# Buttons.net
KiCad netlist of a schematic drawn in Altium Designer
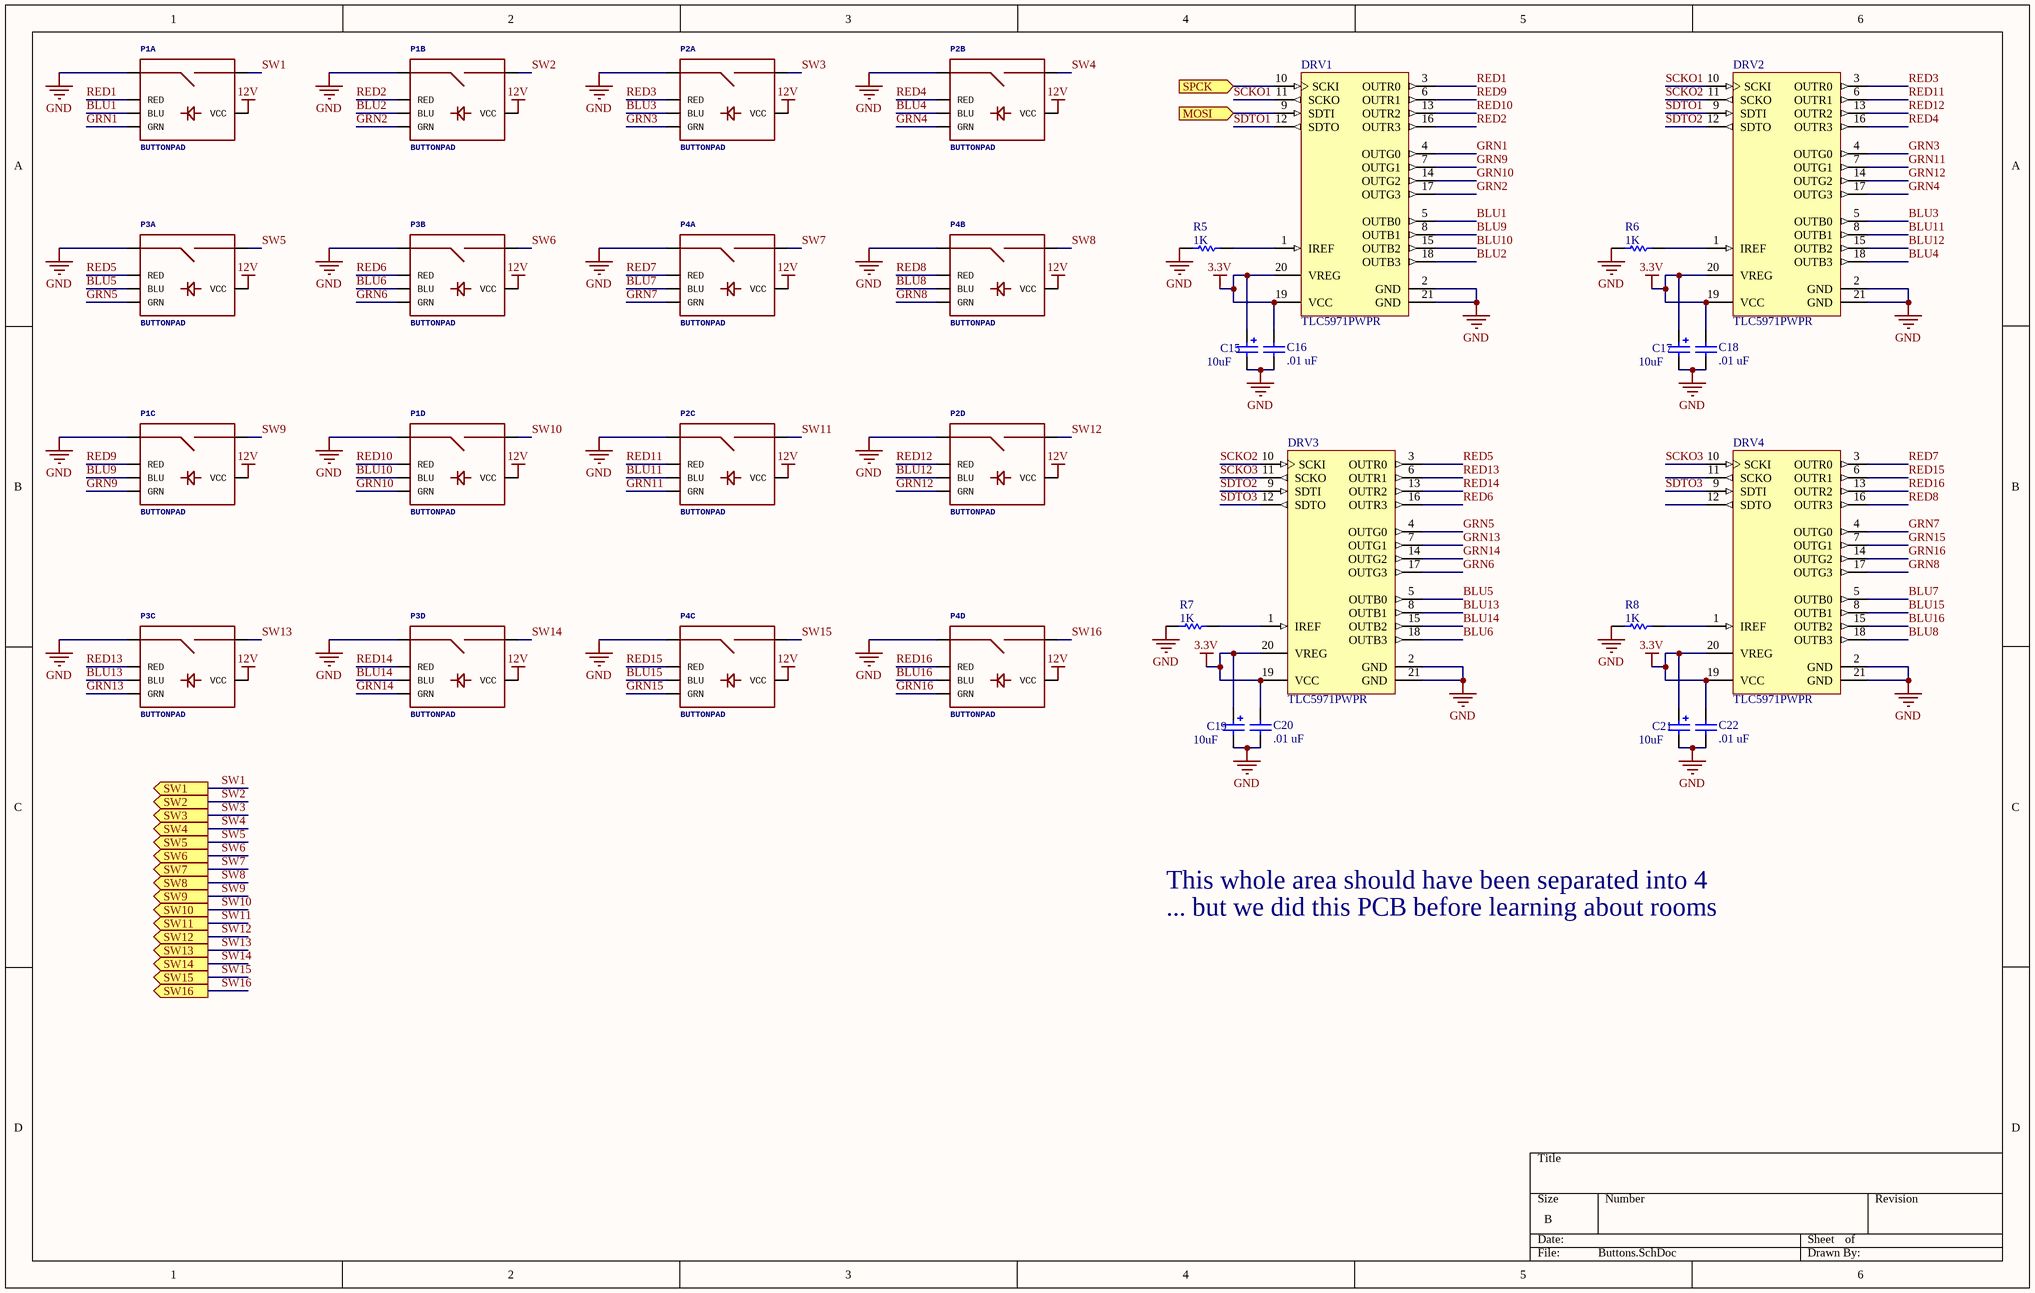
[diagram p0: Buttons.SchDoc]

(export (version "E")
  (design (tool "Eeschema 10.0.6"))
  (components
    (comp (ref "C15")
      (value "10uF")
      (footprint "RAD-0.2")
      (description "Polarized Capacitor (Axial)")
      (fields (field (name "PUBLISHER") "Altium Limited"))
      (libsource (lib "Miscellaneous Devices") (part "Cap Pol2"))
    )
    (comp (ref "C16")
      (value ".01 uF")
      (footprint "C0805")
      (description "Capacitor")
      (fields (field (name "Comment") "Cap") (field (name "PUBLISHER") "Altium Limited"))
      (libsource (lib "Miscellaneous Devices") (part "Cap"))
    )
    (comp (ref "C17")
      (value "10uF")
      (footprint "RAD-0.2")
      (description "Polarized Capacitor (Axial)")
      (fields (field (name "PUBLISHER") "Altium Limited"))
      (libsource (lib "Miscellaneous Devices") (part "Cap Pol2"))
    )
    (comp (ref "C18")
      (value ".01 uF")
      (footprint "C0805")
      (description "Capacitor")
      (fields (field (name "Comment") "Cap") (field (name "PUBLISHER") "Altium Limited"))
      (libsource (lib "Miscellaneous Devices") (part "Cap"))
    )
    (comp (ref "C19")
      (value "10uF")
      (footprint "RAD-0.2")
      (description "Polarized Capacitor (Axial)")
      (fields (field (name "PUBLISHER") "Altium Limited"))
      (libsource (lib "Miscellaneous Devices") (part "Cap Pol2"))
    )
    (comp (ref "C20")
      (value ".01 uF")
      (footprint "C0805")
      (description "Capacitor")
      (fields (field (name "Comment") "Cap") (field (name "PUBLISHER") "Altium Limited"))
      (libsource (lib "Miscellaneous Devices") (part "Cap"))
    )
    (comp (ref "C21")
      (value "10uF")
      (footprint "RAD-0.2")
      (description "Polarized Capacitor (Axial)")
      (fields (field (name "PUBLISHER") "Altium Limited"))
      (libsource (lib "Miscellaneous Devices") (part "Cap Pol2"))
    )
    (comp (ref "C22")
      (value ".01 uF")
      (footprint "C0805")
      (description "Capacitor")
      (fields (field (name "Comment") "Cap") (field (name "PUBLISHER") "Altium Limited"))
      (libsource (lib "Miscellaneous Devices") (part "Cap"))
    )
    (comp (ref "DRV1")
      (value "TLC5971PWPR")
      (footprint "TI-PWP20-2965X2290TP_N")
      (fields (field (name "MANUFACTURER") "Texas Instruments"))
      (libsource (lib "TI Power Management Lighting and Display") (part "TLC5971PWPR"))
    )
    (comp (ref "DRV2")
      (value "TLC5971PWPR")
      (footprint "TI-PWP20-2965X2290TP_N")
      (fields (field (name "MANUFACTURER") "Texas Instruments"))
      (libsource (lib "TI Power Management Lighting and Display") (part "TLC5971PWPR"))
    )
    (comp (ref "DRV3")
      (value "TLC5971PWPR")
      (footprint "TI-PWP20-2965X2290TP_N")
      (fields (field (name "MANUFACTURER") "Texas Instruments"))
      (libsource (lib "TI Power Management Lighting and Display") (part "TLC5971PWPR"))
    )
    (comp (ref "DRV4")
      (value "TLC5971PWPR")
      (footprint "TI-PWP20-2965X2290TP_N")
      (fields (field (name "MANUFACTURER") "Texas Instruments"))
      (libsource (lib "TI Power Management Lighting and Display") (part "TLC5971PWPR"))
    )
    (comp (ref "P1")
      (value "BUTTONPAD")
      (footprint "BUTTONPAD-2X2")
      (libsource (lib "Button_Pad_Breakout-v05") (part "BUTTONPAD-2X2"))
    )
    (comp (ref "P2")
      (value "BUTTONPAD")
      (footprint "BUTTONPAD-2X2")
      (libsource (lib "Button_Pad_Breakout-v05") (part "BUTTONPAD-2X2"))
    )
    (comp (ref "P3")
      (value "BUTTONPAD")
      (footprint "BUTTONPAD-2X2")
      (libsource (lib "Button_Pad_Breakout-v05") (part "BUTTONPAD-2X2"))
    )
    (comp (ref "P4")
      (value "BUTTONPAD")
      (footprint "BUTTONPAD-2X2")
      (libsource (lib "Button_Pad_Breakout-v05") (part "BUTTONPAD-2X2"))
    )
    (comp (ref "R5")
      (value "1K")
      (footprint "AXIAL-0.3")
      (description "Resistor")
      (fields (field (name "Comment") "R1") (field (name "PUBLISHER") "Altium Limited"))
      (libsource (lib "Miscellaneous Devices") (part "Res1"))
    )
    (comp (ref "R6")
      (value "1K")
      (footprint "AXIAL-0.3")
      (description "Resistor")
      (fields (field (name "Comment") "R2") (field (name "PUBLISHER") "Altium Limited"))
      (libsource (lib "Miscellaneous Devices") (part "Res1"))
    )
    (comp (ref "R7")
      (value "1K")
      (footprint "AXIAL-0.3")
      (description "Resistor")
      (fields (field (name "Comment") "R3") (field (name "PUBLISHER") "Altium Limited"))
      (libsource (lib "Miscellaneous Devices") (part "Res1"))
    )
    (comp (ref "R8")
      (value "1K")
      (footprint "AXIAL-0.3")
      (description "Resistor")
      (fields (field (name "Comment") "R4") (field (name "PUBLISHER") "Altium Limited"))
      (libsource (lib "Miscellaneous Devices") (part "Res1"))
    )
  )
  (nets
    (net (code "1") (name "/BLU1") (class "Default")
      (node (ref "DRV1") (pin "5") (pinfunction "OUTB0_5") (pintype "output"))
      (node (ref "P1") (pin "BLU1") (pinfunction "BLU_BLU1") (pintype "passive"))
    )
    (net (code "2") (name "/BLU2") (class "Default")
      (node (ref "DRV1") (pin "18") (pinfunction "OUTB3_18") (pintype "output"))
      (node (ref "P1") (pin "BLU2") (pinfunction "BLU_BLU2") (pintype "passive"))
    )
    (net (code "3") (name "/BLU3") (class "Default")
      (node (ref "DRV2") (pin "5") (pinfunction "OUTB0_5") (pintype "output"))
      (node (ref "P2") (pin "BLU1") (pinfunction "BLU_BLU1") (pintype "passive"))
    )
    (net (code "4") (name "/BLU4") (class "Default")
      (node (ref "DRV2") (pin "18") (pinfunction "OUTB3_18") (pintype "output"))
      (node (ref "P2") (pin "BLU2") (pinfunction "BLU_BLU2") (pintype "passive"))
    )
    (net (code "5") (name "/BLU5") (class "Default")
      (node (ref "DRV3") (pin "5") (pinfunction "OUTB0_5") (pintype "output"))
      (node (ref "P3") (pin "BLU1") (pinfunction "BLU_BLU1") (pintype "passive"))
    )
    (net (code "6") (name "/BLU6") (class "Default")
      (node (ref "DRV3") (pin "18") (pinfunction "OUTB3_18") (pintype "output"))
      (node (ref "P3") (pin "BLU2") (pinfunction "BLU_BLU2") (pintype "passive"))
    )
    (net (code "7") (name "/BLU7") (class "Default")
      (node (ref "DRV4") (pin "5") (pinfunction "OUTB0_5") (pintype "output"))
      (node (ref "P4") (pin "BLU1") (pinfunction "BLU_BLU1") (pintype "passive"))
    )
    (net (code "8") (name "/BLU8") (class "Default")
      (node (ref "DRV4") (pin "18") (pinfunction "OUTB3_18") (pintype "output"))
      (node (ref "P4") (pin "BLU2") (pinfunction "BLU_BLU2") (pintype "passive"))
    )
    (net (code "9") (name "/BLU9") (class "Default")
      (node (ref "DRV1") (pin "8") (pinfunction "OUTB1_8") (pintype "output"))
      (node (ref "P1") (pin "BLU3") (pinfunction "BLU_BLU3") (pintype "passive"))
    )
    (net (code "10") (name "/BLU10") (class "Default")
      (node (ref "DRV1") (pin "15") (pinfunction "OUTB2_15") (pintype "output"))
      (node (ref "P1") (pin "BLU4") (pinfunction "BLU_BLU4") (pintype "passive"))
    )
    (net (code "11") (name "/BLU11") (class "Default")
      (node (ref "DRV2") (pin "8") (pinfunction "OUTB1_8") (pintype "output"))
      (node (ref "P2") (pin "BLU3") (pinfunction "BLU_BLU3") (pintype "passive"))
    )
    (net (code "12") (name "/BLU12") (class "Default")
      (node (ref "DRV2") (pin "15") (pinfunction "OUTB2_15") (pintype "output"))
      (node (ref "P2") (pin "BLU4") (pinfunction "BLU_BLU4") (pintype "passive"))
    )
    (net (code "13") (name "/BLU13") (class "Default")
      (node (ref "DRV3") (pin "8") (pinfunction "OUTB1_8") (pintype "output"))
      (node (ref "P3") (pin "BLU3") (pinfunction "BLU_BLU3") (pintype "passive"))
    )
    (net (code "14") (name "/BLU14") (class "Default")
      (node (ref "DRV3") (pin "15") (pinfunction "OUTB2_15") (pintype "output"))
      (node (ref "P3") (pin "BLU4") (pinfunction "BLU_BLU4") (pintype "passive"))
    )
    (net (code "15") (name "/BLU15") (class "Default")
      (node (ref "DRV4") (pin "8") (pinfunction "OUTB1_8") (pintype "output"))
      (node (ref "P4") (pin "BLU3") (pinfunction "BLU_BLU3") (pintype "passive"))
    )
    (net (code "16") (name "/BLU16") (class "Default")
      (node (ref "DRV4") (pin "15") (pinfunction "OUTB2_15") (pintype "output"))
      (node (ref "P4") (pin "BLU4") (pinfunction "BLU_BLU4") (pintype "passive"))
    )
    (net (code "17") (name "/GRN1") (class "Default")
      (node (ref "DRV1") (pin "4") (pinfunction "OUTG0_4") (pintype "output"))
      (node (ref "P1") (pin "GRN1") (pinfunction "GRN_GRN1") (pintype "passive"))
    )
    (net (code "18") (name "/GRN2") (class "Default")
      (node (ref "DRV1") (pin "17") (pinfunction "OUTG3_17") (pintype "output"))
      (node (ref "P1") (pin "GRN2") (pinfunction "GRN_GRN2") (pintype "passive"))
    )
    (net (code "19") (name "/GRN3") (class "Default")
      (node (ref "DRV2") (pin "4") (pinfunction "OUTG0_4") (pintype "output"))
      (node (ref "P2") (pin "GRN1") (pinfunction "GRN_GRN1") (pintype "passive"))
    )
    (net (code "20") (name "/GRN4") (class "Default")
      (node (ref "DRV2") (pin "17") (pinfunction "OUTG3_17") (pintype "output"))
      (node (ref "P2") (pin "GRN2") (pinfunction "GRN_GRN2") (pintype "passive"))
    )
    (net (code "21") (name "/GRN5") (class "Default")
      (node (ref "DRV3") (pin "4") (pinfunction "OUTG0_4") (pintype "output"))
      (node (ref "P3") (pin "GRN1") (pinfunction "GRN_GRN1") (pintype "passive"))
    )
    (net (code "22") (name "/GRN6") (class "Default")
      (node (ref "DRV3") (pin "17") (pinfunction "OUTG3_17") (pintype "output"))
      (node (ref "P3") (pin "GRN2") (pinfunction "GRN_GRN2") (pintype "passive"))
    )
    (net (code "23") (name "/GRN7") (class "Default")
      (node (ref "DRV4") (pin "4") (pinfunction "OUTG0_4") (pintype "output"))
      (node (ref "P4") (pin "GRN1") (pinfunction "GRN_GRN1") (pintype "passive"))
    )
    (net (code "24") (name "/GRN8") (class "Default")
      (node (ref "DRV4") (pin "17") (pinfunction "OUTG3_17") (pintype "output"))
      (node (ref "P4") (pin "GRN2") (pinfunction "GRN_GRN2") (pintype "passive"))
    )
    (net (code "25") (name "/GRN9") (class "Default")
      (node (ref "DRV1") (pin "7") (pinfunction "OUTG1_7") (pintype "output"))
      (node (ref "P1") (pin "GRN3") (pinfunction "GRN_GRN3") (pintype "passive"))
    )
    (net (code "26") (name "/GRN10") (class "Default")
      (node (ref "DRV1") (pin "14") (pinfunction "OUTG2_14") (pintype "output"))
      (node (ref "P1") (pin "GRN4") (pinfunction "GRN_GRN4") (pintype "passive"))
    )
    (net (code "27") (name "/GRN11") (class "Default")
      (node (ref "DRV2") (pin "7") (pinfunction "OUTG1_7") (pintype "output"))
      (node (ref "P2") (pin "GRN3") (pinfunction "GRN_GRN3") (pintype "passive"))
    )
    (net (code "28") (name "/GRN12") (class "Default")
      (node (ref "DRV2") (pin "14") (pinfunction "OUTG2_14") (pintype "output"))
      (node (ref "P2") (pin "GRN4") (pinfunction "GRN_GRN4") (pintype "passive"))
    )
    (net (code "29") (name "/GRN13") (class "Default")
      (node (ref "DRV3") (pin "7") (pinfunction "OUTG1_7") (pintype "output"))
      (node (ref "P3") (pin "GRN3") (pinfunction "GRN_GRN3") (pintype "passive"))
    )
    (net (code "30") (name "/GRN14") (class "Default")
      (node (ref "DRV3") (pin "14") (pinfunction "OUTG2_14") (pintype "output"))
      (node (ref "P3") (pin "GRN4") (pinfunction "GRN_GRN4") (pintype "passive"))
    )
    (net (code "31") (name "/GRN15") (class "Default")
      (node (ref "DRV4") (pin "7") (pinfunction "OUTG1_7") (pintype "output"))
      (node (ref "P4") (pin "GRN3") (pinfunction "GRN_GRN3") (pintype "passive"))
    )
    (net (code "32") (name "/GRN16") (class "Default")
      (node (ref "DRV4") (pin "14") (pinfunction "OUTG2_14") (pintype "output"))
      (node (ref "P4") (pin "GRN4") (pinfunction "GRN_GRN4") (pintype "passive"))
    )
    (net (code "33") (name "/MOSI") (class "Default")
      (node (ref "DRV1") (pin "9") (pinfunction "SDTI_9") (pintype "input"))
    )
    (net (code "34") (name "/RED1") (class "Default")
      (node (ref "DRV1") (pin "3") (pinfunction "OUTR0_3") (pintype "output"))
      (node (ref "P1") (pin "RED1") (pinfunction "RED_RED1") (pintype "passive"))
    )
    (net (code "35") (name "/RED2") (class "Default")
      (node (ref "DRV1") (pin "16") (pinfunction "OUTR3_16") (pintype "output"))
      (node (ref "P1") (pin "RED2") (pinfunction "RED_RED2") (pintype "passive"))
    )
    (net (code "36") (name "/RED3") (class "Default")
      (node (ref "DRV2") (pin "3") (pinfunction "OUTR0_3") (pintype "output"))
      (node (ref "P2") (pin "RED1") (pinfunction "RED_RED1") (pintype "passive"))
    )
    (net (code "37") (name "/RED4") (class "Default")
      (node (ref "DRV2") (pin "16") (pinfunction "OUTR3_16") (pintype "output"))
      (node (ref "P2") (pin "RED2") (pinfunction "RED_RED2") (pintype "passive"))
    )
    (net (code "38") (name "/RED5") (class "Default")
      (node (ref "DRV3") (pin "3") (pinfunction "OUTR0_3") (pintype "output"))
      (node (ref "P3") (pin "RED1") (pinfunction "RED_RED1") (pintype "passive"))
    )
    (net (code "39") (name "/RED6") (class "Default")
      (node (ref "DRV3") (pin "16") (pinfunction "OUTR3_16") (pintype "output"))
      (node (ref "P3") (pin "RED2") (pinfunction "RED_RED2") (pintype "passive"))
    )
    (net (code "40") (name "/RED7") (class "Default")
      (node (ref "DRV4") (pin "3") (pinfunction "OUTR0_3") (pintype "output"))
      (node (ref "P4") (pin "RED1") (pinfunction "RED_RED1") (pintype "passive"))
    )
    (net (code "41") (name "/RED8") (class "Default")
      (node (ref "DRV4") (pin "16") (pinfunction "OUTR3_16") (pintype "output"))
      (node (ref "P4") (pin "RED2") (pinfunction "RED_RED2") (pintype "passive"))
    )
    (net (code "42") (name "/RED9") (class "Default")
      (node (ref "DRV1") (pin "6") (pinfunction "OUTR1_6") (pintype "output"))
      (node (ref "P1") (pin "RED3") (pinfunction "RED_RED3") (pintype "passive"))
    )
    (net (code "43") (name "/RED10") (class "Default")
      (node (ref "DRV1") (pin "13") (pinfunction "OUTR2_13") (pintype "output"))
      (node (ref "P1") (pin "RED4") (pinfunction "RED_RED4") (pintype "passive"))
    )
    (net (code "44") (name "/RED11") (class "Default")
      (node (ref "DRV2") (pin "6") (pinfunction "OUTR1_6") (pintype "output"))
      (node (ref "P2") (pin "RED3") (pinfunction "RED_RED3") (pintype "passive"))
    )
    (net (code "45") (name "/RED12") (class "Default")
      (node (ref "DRV2") (pin "13") (pinfunction "OUTR2_13") (pintype "output"))
      (node (ref "P2") (pin "RED4") (pinfunction "RED_RED4") (pintype "passive"))
    )
    (net (code "46") (name "/RED13") (class "Default")
      (node (ref "DRV3") (pin "6") (pinfunction "OUTR1_6") (pintype "output"))
      (node (ref "P3") (pin "RED3") (pinfunction "RED_RED3") (pintype "passive"))
    )
    (net (code "47") (name "/RED14") (class "Default")
      (node (ref "DRV3") (pin "13") (pinfunction "OUTR2_13") (pintype "output"))
      (node (ref "P3") (pin "RED4") (pinfunction "RED_RED4") (pintype "passive"))
    )
    (net (code "48") (name "/RED15") (class "Default")
      (node (ref "DRV4") (pin "6") (pinfunction "OUTR1_6") (pintype "output"))
      (node (ref "P4") (pin "RED3") (pinfunction "RED_RED3") (pintype "passive"))
    )
    (net (code "49") (name "/RED16") (class "Default")
      (node (ref "DRV4") (pin "13") (pinfunction "OUTR2_13") (pintype "output"))
      (node (ref "P4") (pin "RED4") (pinfunction "RED_RED4") (pintype "passive"))
    )
    (net (code "50") (name "/SCKO1") (class "Default")
      (node (ref "DRV1") (pin "11") (pinfunction "SCKO_11") (pintype "output"))
      (node (ref "DRV2") (pin "10") (pinfunction "SCKI_10") (pintype "input"))
    )
    (net (code "51") (name "/SCKO2") (class "Default")
      (node (ref "DRV2") (pin "11") (pinfunction "SCKO_11") (pintype "output"))
      (node (ref "DRV3") (pin "10") (pinfunction "SCKI_10") (pintype "input"))
    )
    (net (code "52") (name "/SCKO3") (class "Default")
      (node (ref "DRV3") (pin "11") (pinfunction "SCKO_11") (pintype "output"))
      (node (ref "DRV4") (pin "10") (pinfunction "SCKI_10") (pintype "input"))
    )
    (net (code "53") (name "/SDTO1") (class "Default")
      (node (ref "DRV1") (pin "12") (pinfunction "SDTO_12") (pintype "output"))
      (node (ref "DRV2") (pin "9") (pinfunction "SDTI_9") (pintype "input"))
    )
    (net (code "54") (name "/SDTO2") (class "Default")
      (node (ref "DRV2") (pin "12") (pinfunction "SDTO_12") (pintype "output"))
      (node (ref "DRV3") (pin "9") (pinfunction "SDTI_9") (pintype "input"))
    )
    (net (code "55") (name "/SDTO3") (class "Default")
      (node (ref "DRV3") (pin "12") (pinfunction "SDTO_12") (pintype "output"))
      (node (ref "DRV4") (pin "9") (pinfunction "SDTI_9") (pintype "input"))
    )
    (net (code "56") (name "/SPCK") (class "Default")
      (node (ref "DRV1") (pin "10") (pinfunction "SCKI_10") (pintype "input"))
    )
    (net (code "57") (name "/SW1") (class "Default")
      (node (ref "P1") (pin "SIG2") (pinfunction "SIG2_SIG2") (pintype "passive"))
    )
    (net (code "58") (name "/SW2") (class "Default")
      (node (ref "P1") (pin "SIG4") (pinfunction "SIG2_SIG4") (pintype "passive"))
    )
    (net (code "59") (name "/SW3") (class "Default")
      (node (ref "P2") (pin "SIG2") (pinfunction "SIG2_SIG2") (pintype "passive"))
    )
    (net (code "60") (name "/SW4") (class "Default")
      (node (ref "P2") (pin "SIG4") (pinfunction "SIG2_SIG4") (pintype "passive"))
    )
    (net (code "61") (name "/SW5") (class "Default")
      (node (ref "P3") (pin "SIG2") (pinfunction "SIG2_SIG2") (pintype "passive"))
    )
    (net (code "62") (name "/SW6") (class "Default")
      (node (ref "P3") (pin "SIG4") (pinfunction "SIG2_SIG4") (pintype "passive"))
    )
    (net (code "63") (name "/SW7") (class "Default")
      (node (ref "P4") (pin "SIG2") (pinfunction "SIG2_SIG2") (pintype "passive"))
    )
    (net (code "64") (name "/SW8") (class "Default")
      (node (ref "P4") (pin "SIG4") (pinfunction "SIG2_SIG4") (pintype "passive"))
    )
    (net (code "65") (name "/SW9") (class "Default")
      (node (ref "P1") (pin "SIG6") (pinfunction "SIG2_SIG6") (pintype "passive"))
    )
    (net (code "66") (name "/SW10") (class "Default")
      (node (ref "P1") (pin "SIG8") (pinfunction "SIG2_SIG8") (pintype "passive"))
    )
    (net (code "67") (name "/SW11") (class "Default")
      (node (ref "P2") (pin "SIG6") (pinfunction "SIG2_SIG6") (pintype "passive"))
    )
    (net (code "68") (name "/SW12") (class "Default")
      (node (ref "P2") (pin "SIG8") (pinfunction "SIG2_SIG8") (pintype "passive"))
    )
    (net (code "69") (name "/SW13") (class "Default")
      (node (ref "P3") (pin "SIG6") (pinfunction "SIG2_SIG6") (pintype "passive"))
    )
    (net (code "70") (name "/SW14") (class "Default")
      (node (ref "P3") (pin "SIG8") (pinfunction "SIG2_SIG8") (pintype "passive"))
    )
    (net (code "71") (name "/SW15") (class "Default")
      (node (ref "P4") (pin "SIG6") (pinfunction "SIG2_SIG6") (pintype "passive"))
    )
    (net (code "72") (name "/SW16") (class "Default")
      (node (ref "P4") (pin "SIG8") (pinfunction "SIG2_SIG8") (pintype "passive"))
    )
    (net (code "73") (name "3.3V") (class "Default")
      (node (ref "C15") (pin "1") (pinfunction "1_1") (pintype "passive"))
      (node (ref "C16") (pin "2") (pinfunction "2_2") (pintype "passive"))
      (node (ref "C17") (pin "1") (pinfunction "1_1") (pintype "passive"))
      (node (ref "C18") (pin "2") (pinfunction "2_2") (pintype "passive"))
      (node (ref "C19") (pin "1") (pinfunction "1_1") (pintype "passive"))
      (node (ref "C20") (pin "2") (pinfunction "2_2") (pintype "passive"))
      (node (ref "C21") (pin "1") (pinfunction "1_1") (pintype "passive"))
      (node (ref "C22") (pin "2") (pinfunction "2_2") (pintype "passive"))
      (node (ref "DRV1") (pin "19") (pinfunction "VCC_19") (pintype "power_in"))
      (node (ref "DRV1") (pin "20") (pinfunction "VREG_20") (pintype "power_in"))
      (node (ref "DRV2") (pin "19") (pinfunction "VCC_19") (pintype "power_in"))
      (node (ref "DRV2") (pin "20") (pinfunction "VREG_20") (pintype "power_in"))
      (node (ref "DRV3") (pin "19") (pinfunction "VCC_19") (pintype "power_in"))
      (node (ref "DRV3") (pin "20") (pinfunction "VREG_20") (pintype "power_in"))
      (node (ref "DRV4") (pin "19") (pinfunction "VCC_19") (pintype "power_in"))
      (node (ref "DRV4") (pin "20") (pinfunction "VREG_20") (pintype "power_in"))
    )
    (net (code "74") (name "12V") (class "Default")
      (node (ref "P1") (pin "VCC1") (pinfunction "VCC_VCC1") (pintype "passive"))
      (node (ref "P1") (pin "VCC2") (pinfunction "VCC_VCC2") (pintype "passive"))
      (node (ref "P1") (pin "VCC3") (pinfunction "VCC_VCC3") (pintype "passive"))
      (node (ref "P1") (pin "VCC4") (pinfunction "VCC_VCC4") (pintype "passive"))
      (node (ref "P2") (pin "VCC1") (pinfunction "VCC_VCC1") (pintype "passive"))
      (node (ref "P2") (pin "VCC2") (pinfunction "VCC_VCC2") (pintype "passive"))
      (node (ref "P2") (pin "VCC3") (pinfunction "VCC_VCC3") (pintype "passive"))
      (node (ref "P2") (pin "VCC4") (pinfunction "VCC_VCC4") (pintype "passive"))
      (node (ref "P3") (pin "VCC1") (pinfunction "VCC_VCC1") (pintype "passive"))
      (node (ref "P3") (pin "VCC2") (pinfunction "VCC_VCC2") (pintype "passive"))
      (node (ref "P3") (pin "VCC3") (pinfunction "VCC_VCC3") (pintype "passive"))
      (node (ref "P3") (pin "VCC4") (pinfunction "VCC_VCC4") (pintype "passive"))
      (node (ref "P4") (pin "VCC1") (pinfunction "VCC_VCC1") (pintype "passive"))
      (node (ref "P4") (pin "VCC2") (pinfunction "VCC_VCC2") (pintype "passive"))
      (node (ref "P4") (pin "VCC3") (pinfunction "VCC_VCC3") (pintype "passive"))
      (node (ref "P4") (pin "VCC4") (pinfunction "VCC_VCC4") (pintype "passive"))
    )
    (net (code "75") (name "GND") (class "Default")
      (node (ref "C15") (pin "2") (pinfunction "2_2") (pintype "passive"))
      (node (ref "C16") (pin "1") (pinfunction "1_1") (pintype "passive"))
      (node (ref "C17") (pin "2") (pinfunction "2_2") (pintype "passive"))
      (node (ref "C18") (pin "1") (pinfunction "1_1") (pintype "passive"))
      (node (ref "C19") (pin "2") (pinfunction "2_2") (pintype "passive"))
      (node (ref "C20") (pin "1") (pinfunction "1_1") (pintype "passive"))
      (node (ref "C21") (pin "2") (pinfunction "2_2") (pintype "passive"))
      (node (ref "C22") (pin "1") (pinfunction "1_1") (pintype "passive"))
      (node (ref "DRV1") (pin "2") (pinfunction "GND_2") (pintype "power_in"))
      (node (ref "DRV1") (pin "21") (pinfunction "GND_21") (pintype "power_in"))
      (node (ref "DRV2") (pin "2") (pinfunction "GND_2") (pintype "power_in"))
      (node (ref "DRV2") (pin "21") (pinfunction "GND_21") (pintype "power_in"))
      (node (ref "DRV3") (pin "2") (pinfunction "GND_2") (pintype "power_in"))
      (node (ref "DRV3") (pin "21") (pinfunction "GND_21") (pintype "power_in"))
      (node (ref "DRV4") (pin "2") (pinfunction "GND_2") (pintype "power_in"))
      (node (ref "DRV4") (pin "21") (pinfunction "GND_21") (pintype "power_in"))
      (node (ref "P1") (pin "SIG1") (pinfunction "SIG1_SIG1") (pintype "passive"))
      (node (ref "P1") (pin "SIG3") (pinfunction "SIG1_SIG3") (pintype "passive"))
      (node (ref "P1") (pin "SIG5") (pinfunction "SIG1_SIG5") (pintype "passive"))
      (node (ref "P1") (pin "SIG7") (pinfunction "SIG1_SIG7") (pintype "passive"))
      (node (ref "P2") (pin "SIG1") (pinfunction "SIG1_SIG1") (pintype "passive"))
      (node (ref "P2") (pin "SIG3") (pinfunction "SIG1_SIG3") (pintype "passive"))
      (node (ref "P2") (pin "SIG5") (pinfunction "SIG1_SIG5") (pintype "passive"))
      (node (ref "P2") (pin "SIG7") (pinfunction "SIG1_SIG7") (pintype "passive"))
      (node (ref "P3") (pin "SIG1") (pinfunction "SIG1_SIG1") (pintype "passive"))
      (node (ref "P3") (pin "SIG3") (pinfunction "SIG1_SIG3") (pintype "passive"))
      (node (ref "P3") (pin "SIG5") (pinfunction "SIG1_SIG5") (pintype "passive"))
      (node (ref "P3") (pin "SIG7") (pinfunction "SIG1_SIG7") (pintype "passive"))
      (node (ref "P4") (pin "SIG1") (pinfunction "SIG1_SIG1") (pintype "passive"))
      (node (ref "P4") (pin "SIG3") (pinfunction "SIG1_SIG3") (pintype "passive"))
      (node (ref "P4") (pin "SIG5") (pinfunction "SIG1_SIG5") (pintype "passive"))
      (node (ref "P4") (pin "SIG7") (pinfunction "SIG1_SIG7") (pintype "passive"))
      (node (ref "R5") (pin "1") (pinfunction "1_1") (pintype "passive"))
      (node (ref "R6") (pin "1") (pinfunction "1_1") (pintype "passive"))
      (node (ref "R7") (pin "1") (pinfunction "1_1") (pintype "passive"))
      (node (ref "R8") (pin "1") (pinfunction "1_1") (pintype "passive"))
    )
    (net (code "76") (name "Net-(DRV1-IREF)") (class "Default")
      (node (ref "DRV1") (pin "1") (pinfunction "IREF_1") (pintype "input"))
      (node (ref "R5") (pin "2") (pinfunction "2_2") (pintype "passive"))
    )
    (net (code "77") (name "Net-(DRV2-IREF)") (class "Default")
      (node (ref "DRV2") (pin "1") (pinfunction "IREF_1") (pintype "input"))
      (node (ref "R6") (pin "2") (pinfunction "2_2") (pintype "passive"))
    )
    (net (code "78") (name "Net-(DRV3-IREF)") (class "Default")
      (node (ref "DRV3") (pin "1") (pinfunction "IREF_1") (pintype "input"))
      (node (ref "R7") (pin "2") (pinfunction "2_2") (pintype "passive"))
    )
    (net (code "79") (name "Net-(DRV4-IREF)") (class "Default")
      (node (ref "DRV4") (pin "1") (pinfunction "IREF_1") (pintype "input"))
      (node (ref "R8") (pin "2") (pinfunction "2_2") (pintype "passive"))
    )
    (net (code "80") (name "unconnected-(DRV4-SCKO-Pad11)") (class "Default")
      (node (ref "DRV4") (pin "11") (pinfunction "SCKO_11") (pintype "output"))
    )
    (net (code "81") (name "unconnected-(DRV4-SDTO-Pad12)") (class "Default")
      (node (ref "DRV4") (pin "12") (pinfunction "SDTO_12") (pintype "output"))
    )
  )
)
